# G603A.net
KiCad netlist of a schematic drawn in EAGLE
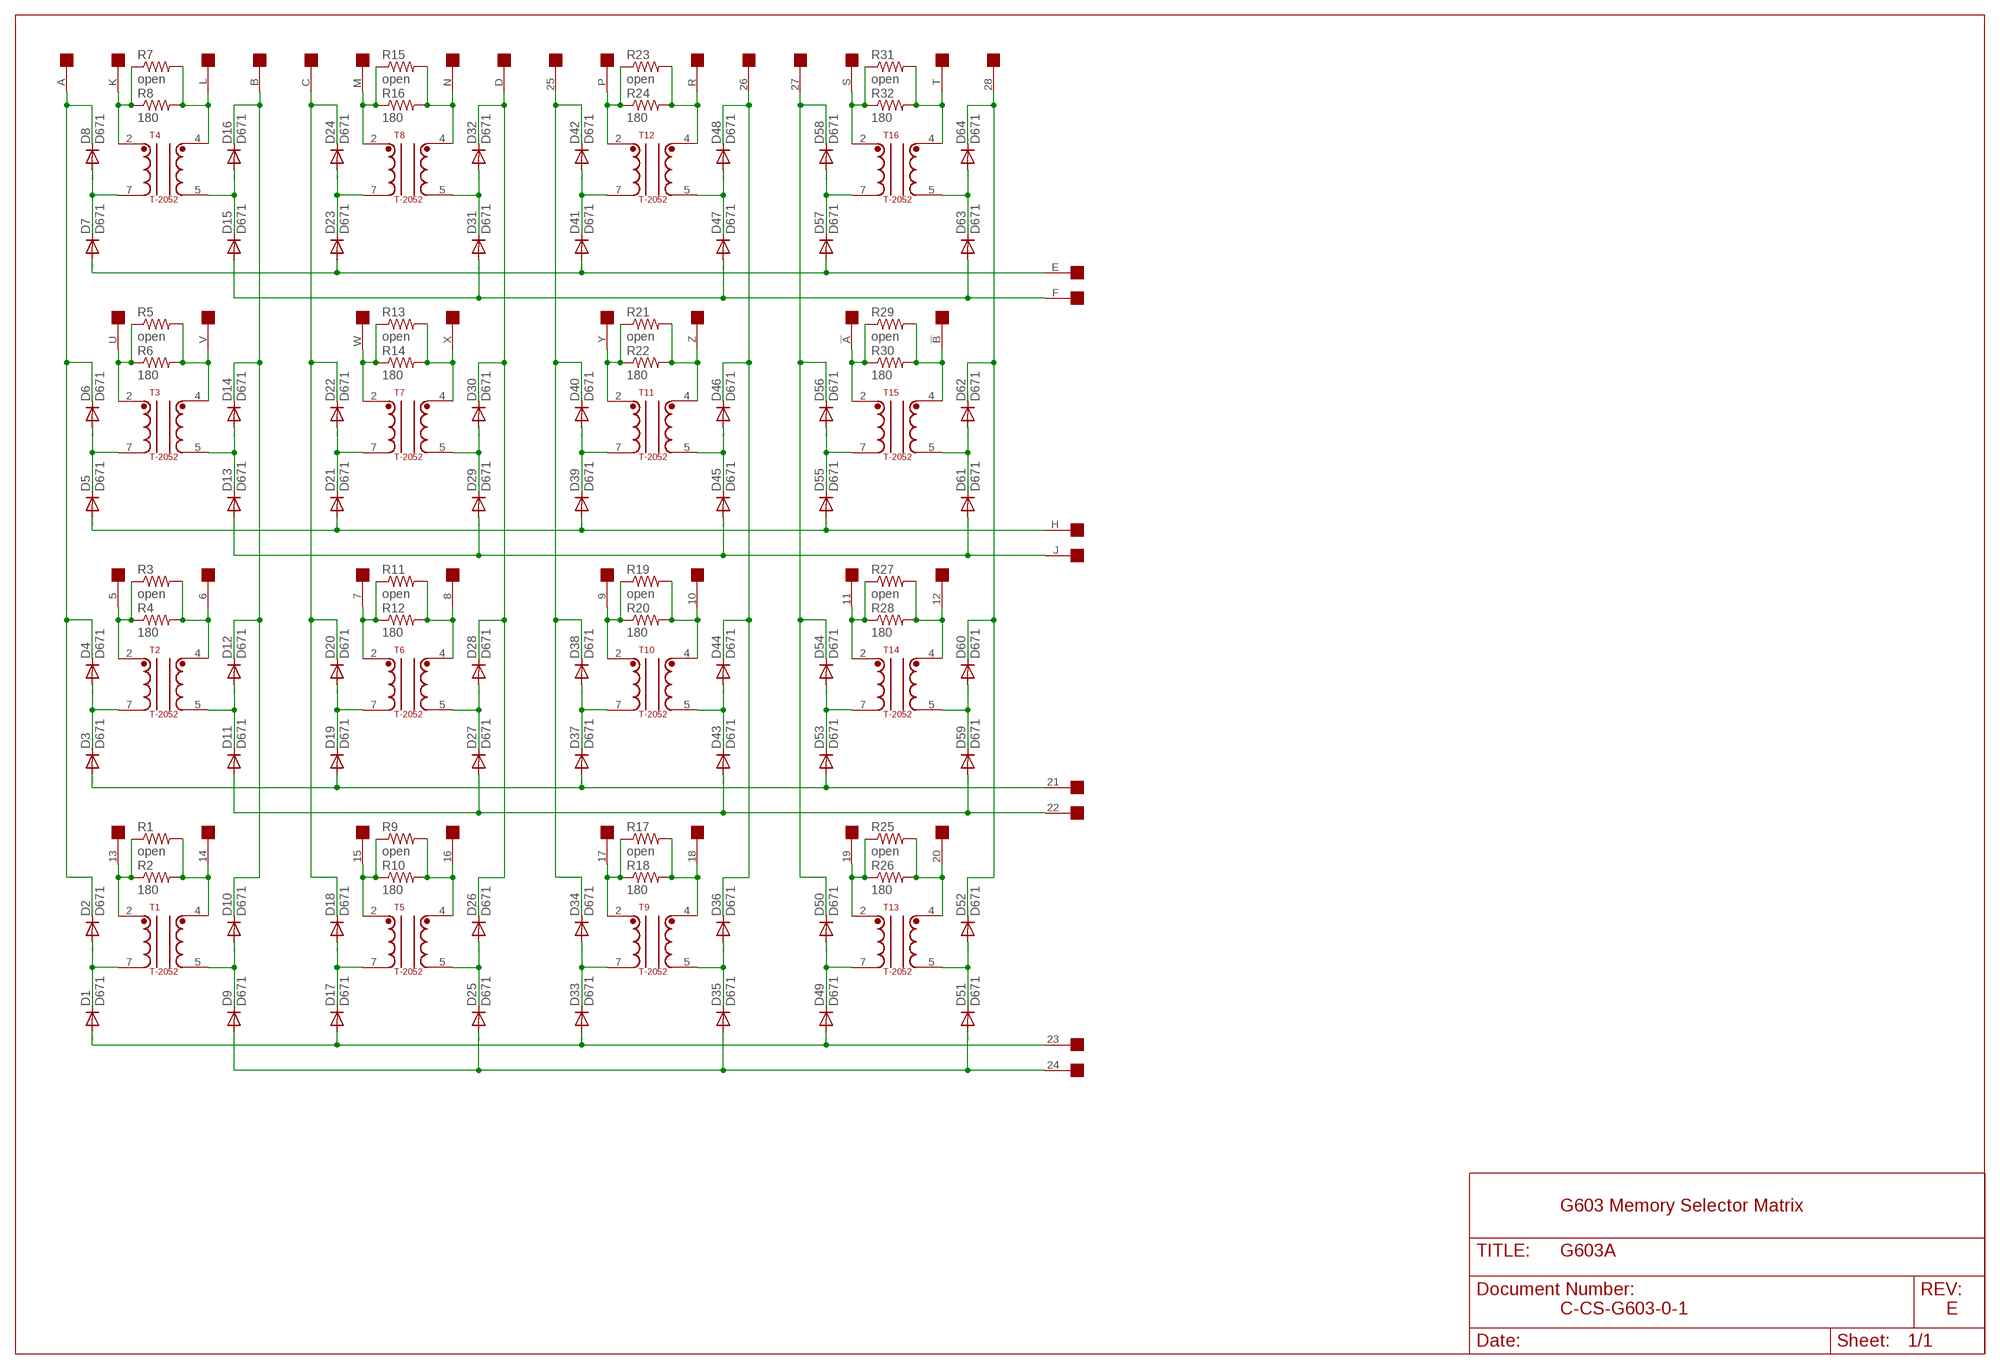
[diagram p0: schematic, sheet 1]

(export (version "E")
  (design (tool "Eeschema 10.0.6"))
  (components
    (comp (ref "D1")
      (value "D671")
      (footprint "eagle-import:DO35-10")
      (libsource (lib "eagle-import") (part "DIODE-DO35-10"))
    )
    (comp (ref "D2")
      (value "D671")
      (footprint "eagle-import:DO35-10")
      (libsource (lib "eagle-import") (part "DIODE-DO35-10"))
    )
    (comp (ref "D3")
      (value "D671")
      (footprint "eagle-import:DO35-10")
      (libsource (lib "eagle-import") (part "DIODE-DO35-10"))
    )
    (comp (ref "D4")
      (value "D671")
      (footprint "eagle-import:DO35-10")
      (libsource (lib "eagle-import") (part "DIODE-DO35-10"))
    )
    (comp (ref "D5")
      (value "D671")
      (footprint "eagle-import:DO35-10")
      (libsource (lib "eagle-import") (part "DIODE-DO35-10"))
    )
    (comp (ref "D6")
      (value "D671")
      (footprint "eagle-import:DO35-10")
      (libsource (lib "eagle-import") (part "DIODE-DO35-10"))
    )
    (comp (ref "D7")
      (value "D671")
      (footprint "eagle-import:DO35-10")
      (libsource (lib "eagle-import") (part "DIODE-DO35-10"))
    )
    (comp (ref "D8")
      (value "D671")
      (footprint "eagle-import:DO35-10")
      (libsource (lib "eagle-import") (part "DIODE-DO35-10"))
    )
    (comp (ref "D9")
      (value "D671")
      (footprint "eagle-import:DO35-10")
      (libsource (lib "eagle-import") (part "DIODE-DO35-10"))
    )
    (comp (ref "D10")
      (value "D671")
      (footprint "eagle-import:DO35-10")
      (libsource (lib "eagle-import") (part "DIODE-DO35-10"))
    )
    (comp (ref "D11")
      (value "D671")
      (footprint "eagle-import:DO35-10")
      (libsource (lib "eagle-import") (part "DIODE-DO35-10"))
    )
    (comp (ref "D12")
      (value "D671")
      (footprint "eagle-import:DO35-10")
      (libsource (lib "eagle-import") (part "DIODE-DO35-10"))
    )
    (comp (ref "D13")
      (value "D671")
      (footprint "eagle-import:DO35-10")
      (libsource (lib "eagle-import") (part "DIODE-DO35-10"))
    )
    (comp (ref "D14")
      (value "D671")
      (footprint "eagle-import:DO35-10")
      (libsource (lib "eagle-import") (part "DIODE-DO35-10"))
    )
    (comp (ref "D15")
      (value "D671")
      (footprint "eagle-import:DO35-10")
      (libsource (lib "eagle-import") (part "DIODE-DO35-10"))
    )
    (comp (ref "D16")
      (value "D671")
      (footprint "eagle-import:DO35-10")
      (libsource (lib "eagle-import") (part "DIODE-DO35-10"))
    )
    (comp (ref "D17")
      (value "D671")
      (footprint "eagle-import:DO35-10")
      (libsource (lib "eagle-import") (part "DIODE-DO35-10"))
    )
    (comp (ref "D18")
      (value "D671")
      (footprint "eagle-import:DO35-10")
      (libsource (lib "eagle-import") (part "DIODE-DO35-10"))
    )
    (comp (ref "D19")
      (value "D671")
      (footprint "eagle-import:DO35-10")
      (libsource (lib "eagle-import") (part "DIODE-DO35-10"))
    )
    (comp (ref "D20")
      (value "D671")
      (footprint "eagle-import:DO35-10")
      (libsource (lib "eagle-import") (part "DIODE-DO35-10"))
    )
    (comp (ref "D21")
      (value "D671")
      (footprint "eagle-import:DO35-10")
      (libsource (lib "eagle-import") (part "DIODE-DO35-10"))
    )
    (comp (ref "D22")
      (value "D671")
      (footprint "eagle-import:DO35-10")
      (libsource (lib "eagle-import") (part "DIODE-DO35-10"))
    )
    (comp (ref "D23")
      (value "D671")
      (footprint "eagle-import:DO35-10")
      (libsource (lib "eagle-import") (part "DIODE-DO35-10"))
    )
    (comp (ref "D24")
      (value "D671")
      (footprint "eagle-import:DO35-10")
      (libsource (lib "eagle-import") (part "DIODE-DO35-10"))
    )
    (comp (ref "D25")
      (value "D671")
      (footprint "eagle-import:DO35-10")
      (libsource (lib "eagle-import") (part "DIODE-DO35-10"))
    )
    (comp (ref "D26")
      (value "D671")
      (footprint "eagle-import:DO35-10")
      (libsource (lib "eagle-import") (part "DIODE-DO35-10"))
    )
    (comp (ref "D27")
      (value "D671")
      (footprint "eagle-import:DO35-10")
      (libsource (lib "eagle-import") (part "DIODE-DO35-10"))
    )
    (comp (ref "D28")
      (value "D671")
      (footprint "eagle-import:DO35-10")
      (libsource (lib "eagle-import") (part "DIODE-DO35-10"))
    )
    (comp (ref "D29")
      (value "D671")
      (footprint "eagle-import:DO35-10")
      (libsource (lib "eagle-import") (part "DIODE-DO35-10"))
    )
    (comp (ref "D30")
      (value "D671")
      (footprint "eagle-import:DO35-10")
      (libsource (lib "eagle-import") (part "DIODE-DO35-10"))
    )
    (comp (ref "D31")
      (value "D671")
      (footprint "eagle-import:DO35-10")
      (libsource (lib "eagle-import") (part "DIODE-DO35-10"))
    )
    (comp (ref "D32")
      (value "D671")
      (footprint "eagle-import:DO35-10")
      (libsource (lib "eagle-import") (part "DIODE-DO35-10"))
    )
    (comp (ref "D33")
      (value "D671")
      (footprint "eagle-import:DO35-10")
      (libsource (lib "eagle-import") (part "DIODE-DO35-10"))
    )
    (comp (ref "D34")
      (value "D671")
      (footprint "eagle-import:DO35-10")
      (libsource (lib "eagle-import") (part "DIODE-DO35-10"))
    )
    (comp (ref "D35")
      (value "D671")
      (footprint "eagle-import:DO35-10")
      (libsource (lib "eagle-import") (part "DIODE-DO35-10"))
    )
    (comp (ref "D36")
      (value "D671")
      (footprint "eagle-import:DO35-10")
      (libsource (lib "eagle-import") (part "DIODE-DO35-10"))
    )
    (comp (ref "D37")
      (value "D671")
      (footprint "eagle-import:DO35-10")
      (libsource (lib "eagle-import") (part "DIODE-DO35-10"))
    )
    (comp (ref "D38")
      (value "D671")
      (footprint "eagle-import:DO35-10")
      (libsource (lib "eagle-import") (part "DIODE-DO35-10"))
    )
    (comp (ref "D39")
      (value "D671")
      (footprint "eagle-import:DO35-10")
      (libsource (lib "eagle-import") (part "DIODE-DO35-10"))
    )
    (comp (ref "D40")
      (value "D671")
      (footprint "eagle-import:DO35-10")
      (libsource (lib "eagle-import") (part "DIODE-DO35-10"))
    )
    (comp (ref "D41")
      (value "D671")
      (footprint "eagle-import:DO35-10")
      (libsource (lib "eagle-import") (part "DIODE-DO35-10"))
    )
    (comp (ref "D42")
      (value "D671")
      (footprint "eagle-import:DO35-10")
      (libsource (lib "eagle-import") (part "DIODE-DO35-10"))
    )
    (comp (ref "D43")
      (value "D671")
      (footprint "eagle-import:DO35-10")
      (libsource (lib "eagle-import") (part "DIODE-DO35-10"))
    )
    (comp (ref "D44")
      (value "D671")
      (footprint "eagle-import:DO35-10")
      (libsource (lib "eagle-import") (part "DIODE-DO35-10"))
    )
    (comp (ref "D45")
      (value "D671")
      (footprint "eagle-import:DO35-10")
      (libsource (lib "eagle-import") (part "DIODE-DO35-10"))
    )
    (comp (ref "D46")
      (value "D671")
      (footprint "eagle-import:DO35-10")
      (libsource (lib "eagle-import") (part "DIODE-DO35-10"))
    )
    (comp (ref "D47")
      (value "D671")
      (footprint "eagle-import:DO35-10")
      (libsource (lib "eagle-import") (part "DIODE-DO35-10"))
    )
    (comp (ref "D48")
      (value "D671")
      (footprint "eagle-import:DO35-10")
      (libsource (lib "eagle-import") (part "DIODE-DO35-10"))
    )
    (comp (ref "D49")
      (value "D671")
      (footprint "eagle-import:DO35-10")
      (libsource (lib "eagle-import") (part "DIODE-DO35-10"))
    )
    (comp (ref "D50")
      (value "D671")
      (footprint "eagle-import:DO35-10")
      (libsource (lib "eagle-import") (part "DIODE-DO35-10"))
    )
    (comp (ref "D51")
      (value "D671")
      (footprint "eagle-import:DO35-10")
      (libsource (lib "eagle-import") (part "DIODE-DO35-10"))
    )
    (comp (ref "D52")
      (value "D671")
      (footprint "eagle-import:DO35-10")
      (libsource (lib "eagle-import") (part "DIODE-DO35-10"))
    )
    (comp (ref "D53")
      (value "D671")
      (footprint "eagle-import:DO35-10")
      (libsource (lib "eagle-import") (part "DIODE-DO35-10"))
    )
    (comp (ref "D54")
      (value "D671")
      (footprint "eagle-import:DO35-10")
      (libsource (lib "eagle-import") (part "DIODE-DO35-10"))
    )
    (comp (ref "D55")
      (value "D671")
      (footprint "eagle-import:DO35-10")
      (libsource (lib "eagle-import") (part "DIODE-DO35-10"))
    )
    (comp (ref "D56")
      (value "D671")
      (footprint "eagle-import:DO35-10")
      (libsource (lib "eagle-import") (part "DIODE-DO35-10"))
    )
    (comp (ref "D57")
      (value "D671")
      (footprint "eagle-import:DO35-10")
      (libsource (lib "eagle-import") (part "DIODE-DO35-10"))
    )
    (comp (ref "D58")
      (value "D671")
      (footprint "eagle-import:DO35-10")
      (libsource (lib "eagle-import") (part "DIODE-DO35-10"))
    )
    (comp (ref "D59")
      (value "D671")
      (footprint "eagle-import:DO35-10")
      (libsource (lib "eagle-import") (part "DIODE-DO35-10"))
    )
    (comp (ref "D60")
      (value "D671")
      (footprint "eagle-import:DO35-10")
      (libsource (lib "eagle-import") (part "DIODE-DO35-10"))
    )
    (comp (ref "D61")
      (value "D671")
      (footprint "eagle-import:DO35-10")
      (libsource (lib "eagle-import") (part "DIODE-DO35-10"))
    )
    (comp (ref "D62")
      (value "D671")
      (footprint "eagle-import:DO35-10")
      (libsource (lib "eagle-import") (part "DIODE-DO35-10"))
    )
    (comp (ref "D63")
      (value "D671")
      (footprint "eagle-import:DO35-10")
      (libsource (lib "eagle-import") (part "DIODE-DO35-10"))
    )
    (comp (ref "D64")
      (value "D671")
      (footprint "eagle-import:DO35-10")
      (libsource (lib "eagle-import") (part "DIODE-DO35-10"))
    )
    (comp (ref "EDGE1")
      (value "MEM8")
      (footprint "eagle-import:MEM8")
      (libsource (lib "eagle-import") (part "MEM8"))
    )
    (comp (ref "R1")
      (value "open")
      (footprint "eagle-import:0207_10")
      (libsource (lib "eagle-import") (part "R-US_0207/10"))
    )
    (comp (ref "R2")
      (value "180")
      (footprint "eagle-import:0207_10")
      (libsource (lib "eagle-import") (part "R-US_0207/10"))
    )
    (comp (ref "R3")
      (value "open")
      (footprint "eagle-import:0207_10")
      (libsource (lib "eagle-import") (part "R-US_0207/10"))
    )
    (comp (ref "R4")
      (value "180")
      (footprint "eagle-import:0207_10")
      (libsource (lib "eagle-import") (part "R-US_0207/10"))
    )
    (comp (ref "R5")
      (value "open")
      (footprint "eagle-import:0207_10")
      (libsource (lib "eagle-import") (part "R-US_0207/10"))
    )
    (comp (ref "R6")
      (value "180")
      (footprint "eagle-import:0207_10")
      (libsource (lib "eagle-import") (part "R-US_0207/10"))
    )
    (comp (ref "R7")
      (value "open")
      (footprint "eagle-import:0207_10")
      (libsource (lib "eagle-import") (part "R-US_0207/10"))
    )
    (comp (ref "R8")
      (value "180")
      (footprint "eagle-import:0207_10")
      (libsource (lib "eagle-import") (part "R-US_0207/10"))
    )
    (comp (ref "R9")
      (value "open")
      (footprint "eagle-import:0207_10")
      (libsource (lib "eagle-import") (part "R-US_0207/10"))
    )
    (comp (ref "R10")
      (value "180")
      (footprint "eagle-import:0207_10")
      (libsource (lib "eagle-import") (part "R-US_0207/10"))
    )
    (comp (ref "R11")
      (value "open")
      (footprint "eagle-import:0207_10")
      (libsource (lib "eagle-import") (part "R-US_0207/10"))
    )
    (comp (ref "R12")
      (value "180")
      (footprint "eagle-import:0207_10")
      (libsource (lib "eagle-import") (part "R-US_0207/10"))
    )
    (comp (ref "R13")
      (value "open")
      (footprint "eagle-import:0207_10")
      (libsource (lib "eagle-import") (part "R-US_0207/10"))
    )
    (comp (ref "R14")
      (value "180")
      (footprint "eagle-import:0207_10")
      (libsource (lib "eagle-import") (part "R-US_0207/10"))
    )
    (comp (ref "R15")
      (value "open")
      (footprint "eagle-import:0207_10")
      (libsource (lib "eagle-import") (part "R-US_0207/10"))
    )
    (comp (ref "R16")
      (value "180")
      (footprint "eagle-import:0207_10")
      (libsource (lib "eagle-import") (part "R-US_0207/10"))
    )
    (comp (ref "R17")
      (value "open")
      (footprint "eagle-import:0207_10")
      (libsource (lib "eagle-import") (part "R-US_0207/10"))
    )
    (comp (ref "R18")
      (value "180")
      (footprint "eagle-import:0207_10")
      (libsource (lib "eagle-import") (part "R-US_0207/10"))
    )
    (comp (ref "R19")
      (value "open")
      (footprint "eagle-import:0207_10")
      (libsource (lib "eagle-import") (part "R-US_0207/10"))
    )
    (comp (ref "R20")
      (value "180")
      (footprint "eagle-import:0207_10")
      (libsource (lib "eagle-import") (part "R-US_0207/10"))
    )
    (comp (ref "R21")
      (value "open")
      (footprint "eagle-import:0207_10")
      (libsource (lib "eagle-import") (part "R-US_0207/10"))
    )
    (comp (ref "R22")
      (value "180")
      (footprint "eagle-import:0207_10")
      (libsource (lib "eagle-import") (part "R-US_0207/10"))
    )
    (comp (ref "R23")
      (value "open")
      (footprint "eagle-import:0207_10")
      (libsource (lib "eagle-import") (part "R-US_0207/10"))
    )
    (comp (ref "R24")
      (value "180")
      (footprint "eagle-import:0207_10")
      (libsource (lib "eagle-import") (part "R-US_0207/10"))
    )
    (comp (ref "R25")
      (value "open")
      (footprint "eagle-import:0207_10")
      (libsource (lib "eagle-import") (part "R-US_0207/10"))
    )
    (comp (ref "R26")
      (value "180")
      (footprint "eagle-import:0207_10")
      (libsource (lib "eagle-import") (part "R-US_0207/10"))
    )
    (comp (ref "R27")
      (value "open")
      (footprint "eagle-import:0207_10")
      (libsource (lib "eagle-import") (part "R-US_0207/10"))
    )
    (comp (ref "R28")
      (value "180")
      (footprint "eagle-import:0207_10")
      (libsource (lib "eagle-import") (part "R-US_0207/10"))
    )
    (comp (ref "R29")
      (value "open")
      (footprint "eagle-import:0207_10")
      (libsource (lib "eagle-import") (part "R-US_0207/10"))
    )
    (comp (ref "R30")
      (value "180")
      (footprint "eagle-import:0207_10")
      (libsource (lib "eagle-import") (part "R-US_0207/10"))
    )
    (comp (ref "R31")
      (value "open")
      (footprint "eagle-import:0207_10")
      (libsource (lib "eagle-import") (part "R-US_0207/10"))
    )
    (comp (ref "R32")
      (value "180")
      (footprint "eagle-import:0207_10")
      (libsource (lib "eagle-import") (part "R-US_0207/10"))
    )
    (comp (ref "T1")
      (value "T-2052")
      (footprint "eagle-import:TRANSFORMER")
      (libsource (lib "eagle-import") (part "T-2052"))
    )
    (comp (ref "T2")
      (value "T-2052")
      (footprint "eagle-import:TRANSFORMER")
      (libsource (lib "eagle-import") (part "T-2052"))
    )
    (comp (ref "T3")
      (value "T-2052")
      (footprint "eagle-import:TRANSFORMER")
      (libsource (lib "eagle-import") (part "T-2052"))
    )
    (comp (ref "T4")
      (value "T-2052")
      (footprint "eagle-import:TRANSFORMER")
      (libsource (lib "eagle-import") (part "T-2052"))
    )
    (comp (ref "T5")
      (value "T-2052")
      (footprint "eagle-import:TRANSFORMER")
      (libsource (lib "eagle-import") (part "T-2052"))
    )
    (comp (ref "T6")
      (value "T-2052")
      (footprint "eagle-import:TRANSFORMER")
      (libsource (lib "eagle-import") (part "T-2052"))
    )
    (comp (ref "T7")
      (value "T-2052")
      (footprint "eagle-import:TRANSFORMER")
      (libsource (lib "eagle-import") (part "T-2052"))
    )
    (comp (ref "T8")
      (value "T-2052")
      (footprint "eagle-import:TRANSFORMER")
      (libsource (lib "eagle-import") (part "T-2052"))
    )
    (comp (ref "T9")
      (value "T-2052")
      (footprint "eagle-import:TRANSFORMER")
      (libsource (lib "eagle-import") (part "T-2052"))
    )
    (comp (ref "T10")
      (value "T-2052")
      (footprint "eagle-import:TRANSFORMER")
      (libsource (lib "eagle-import") (part "T-2052"))
    )
    (comp (ref "T11")
      (value "T-2052")
      (footprint "eagle-import:TRANSFORMER")
      (libsource (lib "eagle-import") (part "T-2052"))
    )
    (comp (ref "T12")
      (value "T-2052")
      (footprint "eagle-import:TRANSFORMER")
      (libsource (lib "eagle-import") (part "T-2052"))
    )
    (comp (ref "T13")
      (value "T-2052")
      (footprint "eagle-import:TRANSFORMER")
      (libsource (lib "eagle-import") (part "T-2052"))
    )
    (comp (ref "T14")
      (value "T-2052")
      (footprint "eagle-import:TRANSFORMER")
      (libsource (lib "eagle-import") (part "T-2052"))
    )
    (comp (ref "T15")
      (value "T-2052")
      (footprint "eagle-import:TRANSFORMER")
      (libsource (lib "eagle-import") (part "T-2052"))
    )
    (comp (ref "T16")
      (value "T-2052")
      (footprint "eagle-import:TRANSFORMER")
      (libsource (lib "eagle-import") (part "T-2052"))
    )
  )
  (nets
    (net (code "1") (name "Net-(EDGE1A-1)") (class "Default")
      (node (ref "EDGE1") (pin "!A") (pinfunction "1_!A") (pintype "bidirectional"))
      (node (ref "R29") (pin "1") (pinfunction "1_1") (pintype "passive"))
      (node (ref "R30") (pin "1") (pinfunction "1_1") (pintype "passive"))
      (node (ref "T15") (pin "2") (pinfunction "P$2_2") (pintype "passive"))
    )
    (net (code "2") (name "Net-(EDGE1AA-1)") (class "Default")
      (node (ref "D52") (pin "C") (pinfunction "C_C") (pintype "passive"))
      (node (ref "D60") (pin "C") (pinfunction "C_C") (pintype "passive"))
      (node (ref "D62") (pin "C") (pinfunction "C_C") (pintype "passive"))
      (node (ref "D64") (pin "C") (pinfunction "C_C") (pintype "passive"))
      (node (ref "EDGE1") (pin "28") (pinfunction "1_28") (pintype "bidirectional"))
    )
    (net (code "3") (name "Net-(EDGE1AD-1)") (class "Default")
      (node (ref "EDGE1") (pin "5") (pinfunction "1_5") (pintype "bidirectional"))
      (node (ref "R3") (pin "1") (pinfunction "1_1") (pintype "passive"))
      (node (ref "R4") (pin "1") (pinfunction "1_1") (pintype "passive"))
      (node (ref "T2") (pin "2") (pinfunction "P$2_2") (pintype "passive"))
    )
    (net (code "4") (name "Net-(EDGE1AE-1)") (class "Default")
      (node (ref "EDGE1") (pin "6") (pinfunction "1_6") (pintype "bidirectional"))
      (node (ref "R3") (pin "2") (pinfunction "2_2") (pintype "passive"))
      (node (ref "R4") (pin "2") (pinfunction "2_2") (pintype "passive"))
      (node (ref "T2") (pin "4") (pinfunction "P$4_4") (pintype "passive"))
    )
    (net (code "5") (name "Net-(EDGE1AF-1)") (class "Default")
      (node (ref "EDGE1") (pin "7") (pinfunction "1_7") (pintype "bidirectional"))
      (node (ref "R11") (pin "1") (pinfunction "1_1") (pintype "passive"))
      (node (ref "R12") (pin "1") (pinfunction "1_1") (pintype "passive"))
      (node (ref "T6") (pin "2") (pinfunction "P$2_2") (pintype "passive"))
    )
    (net (code "6") (name "Net-(EDGE1AG-1)") (class "Default")
      (node (ref "EDGE1") (pin "8") (pinfunction "1_8") (pintype "bidirectional"))
      (node (ref "R11") (pin "2") (pinfunction "2_2") (pintype "passive"))
      (node (ref "R12") (pin "2") (pinfunction "2_2") (pintype "passive"))
      (node (ref "T6") (pin "4") (pinfunction "P$4_4") (pintype "passive"))
    )
    (net (code "7") (name "Net-(EDGE1AH-1)") (class "Default")
      (node (ref "EDGE1") (pin "9") (pinfunction "1_9") (pintype "bidirectional"))
      (node (ref "R19") (pin "1") (pinfunction "1_1") (pintype "passive"))
      (node (ref "R20") (pin "1") (pinfunction "1_1") (pintype "passive"))
      (node (ref "T10") (pin "2") (pinfunction "P$2_2") (pintype "passive"))
    )
    (net (code "8") (name "Net-(EDGE1AI-1)") (class "Default")
      (node (ref "D2") (pin "C") (pinfunction "C_C") (pintype "passive"))
      (node (ref "D4") (pin "C") (pinfunction "C_C") (pintype "passive"))
      (node (ref "D6") (pin "C") (pinfunction "C_C") (pintype "passive"))
      (node (ref "D8") (pin "C") (pinfunction "C_C") (pintype "passive"))
      (node (ref "EDGE1") (pin "A") (pinfunction "1_A") (pintype "bidirectional"))
    )
    (net (code "9") (name "Net-(EDGE1AJ-1)") (class "Default")
      (node (ref "D10") (pin "C") (pinfunction "C_C") (pintype "passive"))
      (node (ref "D12") (pin "C") (pinfunction "C_C") (pintype "passive"))
      (node (ref "D14") (pin "C") (pinfunction "C_C") (pintype "passive"))
      (node (ref "D16") (pin "C") (pinfunction "C_C") (pintype "passive"))
      (node (ref "EDGE1") (pin "B") (pinfunction "1_B") (pintype "bidirectional"))
    )
    (net (code "10") (name "Net-(EDGE1AK-1)") (class "Default")
      (node (ref "D18") (pin "C") (pinfunction "C_C") (pintype "passive"))
      (node (ref "D20") (pin "C") (pinfunction "C_C") (pintype "passive"))
      (node (ref "D22") (pin "C") (pinfunction "C_C") (pintype "passive"))
      (node (ref "D24") (pin "C") (pinfunction "C_C") (pintype "passive"))
      (node (ref "EDGE1") (pin "C") (pinfunction "1_C") (pintype "bidirectional"))
    )
    (net (code "11") (name "Net-(EDGE1AL-1)") (class "Default")
      (node (ref "D26") (pin "C") (pinfunction "C_C") (pintype "passive"))
      (node (ref "D28") (pin "C") (pinfunction "C_C") (pintype "passive"))
      (node (ref "D30") (pin "C") (pinfunction "C_C") (pintype "passive"))
      (node (ref "D32") (pin "C") (pinfunction "C_C") (pintype "passive"))
      (node (ref "EDGE1") (pin "D") (pinfunction "1_D") (pintype "bidirectional"))
    )
    (net (code "12") (name "Net-(EDGE1AM-1)") (class "Default")
      (node (ref "D23") (pin "A") (pinfunction "A_A") (pintype "passive"))
      (node (ref "D41") (pin "A") (pinfunction "A_A") (pintype "passive"))
      (node (ref "D57") (pin "A") (pinfunction "A_A") (pintype "passive"))
      (node (ref "D7") (pin "A") (pinfunction "A_A") (pintype "passive"))
      (node (ref "EDGE1") (pin "E") (pinfunction "1_E") (pintype "bidirectional"))
    )
    (net (code "13") (name "Net-(EDGE1AN-1)") (class "Default")
      (node (ref "D15") (pin "A") (pinfunction "A_A") (pintype "passive"))
      (node (ref "D31") (pin "A") (pinfunction "A_A") (pintype "passive"))
      (node (ref "D47") (pin "A") (pinfunction "A_A") (pintype "passive"))
      (node (ref "D63") (pin "A") (pinfunction "A_A") (pintype "passive"))
      (node (ref "EDGE1") (pin "F") (pinfunction "1_F") (pintype "bidirectional"))
    )
    (net (code "14") (name "Net-(EDGE1AO-1)") (class "Default")
      (node (ref "D21") (pin "A") (pinfunction "A_A") (pintype "passive"))
      (node (ref "D39") (pin "A") (pinfunction "A_A") (pintype "passive"))
      (node (ref "D5") (pin "A") (pinfunction "A_A") (pintype "passive"))
      (node (ref "D55") (pin "A") (pinfunction "A_A") (pintype "passive"))
      (node (ref "EDGE1") (pin "H") (pinfunction "1_H") (pintype "bidirectional"))
    )
    (net (code "15") (name "Net-(EDGE1AP-1)") (class "Default")
      (node (ref "D13") (pin "A") (pinfunction "A_A") (pintype "passive"))
      (node (ref "D29") (pin "A") (pinfunction "A_A") (pintype "passive"))
      (node (ref "D45") (pin "A") (pinfunction "A_A") (pintype "passive"))
      (node (ref "D61") (pin "A") (pinfunction "A_A") (pintype "passive"))
      (node (ref "EDGE1") (pin "J") (pinfunction "1_J") (pintype "bidirectional"))
    )
    (net (code "16") (name "Net-(EDGE1AQ-1)") (class "Default")
      (node (ref "EDGE1") (pin "K") (pinfunction "1_K") (pintype "bidirectional"))
      (node (ref "R7") (pin "1") (pinfunction "1_1") (pintype "passive"))
      (node (ref "R8") (pin "1") (pinfunction "1_1") (pintype "passive"))
      (node (ref "T4") (pin "2") (pinfunction "P$2_2") (pintype "passive"))
    )
    (net (code "17") (name "Net-(EDGE1AR-1)") (class "Default")
      (node (ref "EDGE1") (pin "L") (pinfunction "1_L") (pintype "bidirectional"))
      (node (ref "R7") (pin "2") (pinfunction "2_2") (pintype "passive"))
      (node (ref "R8") (pin "2") (pinfunction "2_2") (pintype "passive"))
      (node (ref "T4") (pin "4") (pinfunction "P$4_4") (pintype "passive"))
    )
    (net (code "18") (name "Net-(EDGE1AS-1)") (class "Default")
      (node (ref "EDGE1") (pin "M") (pinfunction "1_M") (pintype "bidirectional"))
      (node (ref "R15") (pin "1") (pinfunction "1_1") (pintype "passive"))
      (node (ref "R16") (pin "1") (pinfunction "1_1") (pintype "passive"))
      (node (ref "T8") (pin "2") (pinfunction "P$2_2") (pintype "passive"))
    )
    (net (code "19") (name "Net-(EDGE1AT-1)") (class "Default")
      (node (ref "EDGE1") (pin "N") (pinfunction "1_N") (pintype "bidirectional"))
      (node (ref "R15") (pin "2") (pinfunction "2_2") (pintype "passive"))
      (node (ref "R16") (pin "2") (pinfunction "2_2") (pintype "passive"))
      (node (ref "T8") (pin "4") (pinfunction "P$4_4") (pintype "passive"))
    )
    (net (code "20") (name "Net-(EDGE1AU-1)") (class "Default")
      (node (ref "EDGE1") (pin "P") (pinfunction "1_P") (pintype "bidirectional"))
      (node (ref "R23") (pin "1") (pinfunction "1_1") (pintype "passive"))
      (node (ref "R24") (pin "1") (pinfunction "1_1") (pintype "passive"))
      (node (ref "T12") (pin "2") (pinfunction "P$2_2") (pintype "passive"))
    )
    (net (code "21") (name "Net-(EDGE1AV-1)") (class "Default")
      (node (ref "EDGE1") (pin "R") (pinfunction "1_R") (pintype "bidirectional"))
      (node (ref "R23") (pin "2") (pinfunction "2_2") (pintype "passive"))
      (node (ref "R24") (pin "2") (pinfunction "2_2") (pintype "passive"))
      (node (ref "T12") (pin "4") (pinfunction "P$4_4") (pintype "passive"))
    )
    (net (code "22") (name "Net-(EDGE1AW-1)") (class "Default")
      (node (ref "EDGE1") (pin "S") (pinfunction "1_S") (pintype "bidirectional"))
      (node (ref "R31") (pin "1") (pinfunction "1_1") (pintype "passive"))
      (node (ref "R32") (pin "1") (pinfunction "1_1") (pintype "passive"))
      (node (ref "T16") (pin "2") (pinfunction "P$2_2") (pintype "passive"))
    )
    (net (code "23") (name "Net-(EDGE1AX-1)") (class "Default")
      (node (ref "EDGE1") (pin "T") (pinfunction "1_T") (pintype "bidirectional"))
      (node (ref "R31") (pin "2") (pinfunction "2_2") (pintype "passive"))
      (node (ref "R32") (pin "2") (pinfunction "2_2") (pintype "passive"))
      (node (ref "T16") (pin "4") (pinfunction "P$4_4") (pintype "passive"))
    )
    (net (code "24") (name "Net-(EDGE1AY-1)") (class "Default")
      (node (ref "EDGE1") (pin "U") (pinfunction "1_U") (pintype "bidirectional"))
      (node (ref "R5") (pin "1") (pinfunction "1_1") (pintype "passive"))
      (node (ref "R6") (pin "1") (pinfunction "1_1") (pintype "passive"))
      (node (ref "T3") (pin "2") (pinfunction "P$2_2") (pintype "passive"))
    )
    (net (code "25") (name "Net-(EDGE1AZ-1)") (class "Default")
      (node (ref "EDGE1") (pin "V") (pinfunction "1_V") (pintype "bidirectional"))
      (node (ref "R5") (pin "2") (pinfunction "2_2") (pintype "passive"))
      (node (ref "R6") (pin "2") (pinfunction "2_2") (pintype "passive"))
      (node (ref "T3") (pin "4") (pinfunction "P$4_4") (pintype "passive"))
    )
    (net (code "26") (name "Net-(EDGE1B-1)") (class "Default")
      (node (ref "EDGE1") (pin "!B") (pinfunction "1_!B") (pintype "bidirectional"))
      (node (ref "R29") (pin "2") (pinfunction "2_2") (pintype "passive"))
      (node (ref "R30") (pin "2") (pinfunction "2_2") (pintype "passive"))
      (node (ref "T15") (pin "4") (pinfunction "P$4_4") (pintype "passive"))
    )
    (net (code "27") (name "Net-(EDGE1BA-1)") (class "Default")
      (node (ref "EDGE1") (pin "W") (pinfunction "1_W") (pintype "bidirectional"))
      (node (ref "R13") (pin "1") (pinfunction "1_1") (pintype "passive"))
      (node (ref "R14") (pin "1") (pinfunction "1_1") (pintype "passive"))
      (node (ref "T7") (pin "2") (pinfunction "P$2_2") (pintype "passive"))
    )
    (net (code "28") (name "Net-(EDGE1BB-1)") (class "Default")
      (node (ref "EDGE1") (pin "X") (pinfunction "1_X") (pintype "bidirectional"))
      (node (ref "R13") (pin "2") (pinfunction "2_2") (pintype "passive"))
      (node (ref "R14") (pin "2") (pinfunction "2_2") (pintype "passive"))
      (node (ref "T7") (pin "4") (pinfunction "P$4_4") (pintype "passive"))
    )
    (net (code "29") (name "Net-(EDGE1BC-1)") (class "Default")
      (node (ref "EDGE1") (pin "Y") (pinfunction "1_Y") (pintype "bidirectional"))
      (node (ref "R21") (pin "1") (pinfunction "1_1") (pintype "passive"))
      (node (ref "R22") (pin "1") (pinfunction "1_1") (pintype "passive"))
      (node (ref "T11") (pin "2") (pinfunction "P$2_2") (pintype "passive"))
    )
    (net (code "30") (name "Net-(EDGE1BD-1)") (class "Default")
      (node (ref "EDGE1") (pin "Z") (pinfunction "1_Z") (pintype "bidirectional"))
      (node (ref "R21") (pin "2") (pinfunction "2_2") (pintype "passive"))
      (node (ref "R22") (pin "2") (pinfunction "2_2") (pintype "passive"))
      (node (ref "T11") (pin "4") (pinfunction "P$4_4") (pintype "passive"))
    )
    (net (code "31") (name "Net-(EDGE1H-1)") (class "Default")
      (node (ref "EDGE1") (pin "10") (pinfunction "1_10") (pintype "bidirectional"))
      (node (ref "R19") (pin "2") (pinfunction "2_2") (pintype "passive"))
      (node (ref "R20") (pin "2") (pinfunction "2_2") (pintype "passive"))
      (node (ref "T10") (pin "4") (pinfunction "P$4_4") (pintype "passive"))
    )
    (net (code "32") (name "Net-(EDGE1I-1)") (class "Default")
      (node (ref "EDGE1") (pin "11") (pinfunction "1_11") (pintype "bidirectional"))
      (node (ref "R27") (pin "1") (pinfunction "1_1") (pintype "passive"))
      (node (ref "R28") (pin "1") (pinfunction "1_1") (pintype "passive"))
      (node (ref "T14") (pin "2") (pinfunction "P$2_2") (pintype "passive"))
    )
    (net (code "33") (name "Net-(EDGE1J-1)") (class "Default")
      (node (ref "EDGE1") (pin "12") (pinfunction "1_12") (pintype "bidirectional"))
      (node (ref "R27") (pin "2") (pinfunction "2_2") (pintype "passive"))
      (node (ref "R28") (pin "2") (pinfunction "2_2") (pintype "passive"))
      (node (ref "T14") (pin "4") (pinfunction "P$4_4") (pintype "passive"))
    )
    (net (code "34") (name "Net-(EDGE1K-1)") (class "Default")
      (node (ref "EDGE1") (pin "13") (pinfunction "1_13") (pintype "bidirectional"))
      (node (ref "R1") (pin "1") (pinfunction "1_1") (pintype "passive"))
      (node (ref "R2") (pin "1") (pinfunction "1_1") (pintype "passive"))
      (node (ref "T1") (pin "2") (pinfunction "P$2_2") (pintype "passive"))
    )
    (net (code "35") (name "Net-(EDGE1L-1)") (class "Default")
      (node (ref "EDGE1") (pin "14") (pinfunction "1_14") (pintype "bidirectional"))
      (node (ref "R1") (pin "2") (pinfunction "2_2") (pintype "passive"))
      (node (ref "R2") (pin "2") (pinfunction "2_2") (pintype "passive"))
      (node (ref "T1") (pin "4") (pinfunction "P$4_4") (pintype "passive"))
    )
    (net (code "36") (name "Net-(EDGE1M-1)") (class "Default")
      (node (ref "EDGE1") (pin "15") (pinfunction "1_15") (pintype "bidirectional"))
      (node (ref "R10") (pin "1") (pinfunction "1_1") (pintype "passive"))
      (node (ref "R9") (pin "1") (pinfunction "1_1") (pintype "passive"))
      (node (ref "T5") (pin "2") (pinfunction "P$2_2") (pintype "passive"))
    )
    (net (code "37") (name "Net-(EDGE1N-1)") (class "Default")
      (node (ref "EDGE1") (pin "16") (pinfunction "1_16") (pintype "bidirectional"))
      (node (ref "R10") (pin "2") (pinfunction "2_2") (pintype "passive"))
      (node (ref "R9") (pin "2") (pinfunction "2_2") (pintype "passive"))
      (node (ref "T5") (pin "4") (pinfunction "P$4_4") (pintype "passive"))
    )
    (net (code "38") (name "Net-(EDGE1O-1)") (class "Default")
      (node (ref "EDGE1") (pin "17") (pinfunction "1_17") (pintype "bidirectional"))
      (node (ref "R17") (pin "1") (pinfunction "1_1") (pintype "passive"))
      (node (ref "R18") (pin "1") (pinfunction "1_1") (pintype "passive"))
      (node (ref "T9") (pin "2") (pinfunction "P$2_2") (pintype "passive"))
    )
    (net (code "39") (name "Net-(EDGE1P-1)") (class "Default")
      (node (ref "EDGE1") (pin "18") (pinfunction "1_18") (pintype "bidirectional"))
      (node (ref "R17") (pin "2") (pinfunction "2_2") (pintype "passive"))
      (node (ref "R18") (pin "2") (pinfunction "2_2") (pintype "passive"))
      (node (ref "T9") (pin "4") (pinfunction "P$4_4") (pintype "passive"))
    )
    (net (code "40") (name "Net-(EDGE1Q-1)") (class "Default")
      (node (ref "EDGE1") (pin "19") (pinfunction "1_19") (pintype "bidirectional"))
      (node (ref "R25") (pin "1") (pinfunction "1_1") (pintype "passive"))
      (node (ref "R26") (pin "1") (pinfunction "1_1") (pintype "passive"))
      (node (ref "T13") (pin "2") (pinfunction "P$2_2") (pintype "passive"))
    )
    (net (code "41") (name "Net-(EDGE1S-1)") (class "Default")
      (node (ref "EDGE1") (pin "20") (pinfunction "1_20") (pintype "bidirectional"))
      (node (ref "R25") (pin "2") (pinfunction "2_2") (pintype "passive"))
      (node (ref "R26") (pin "2") (pinfunction "2_2") (pintype "passive"))
      (node (ref "T13") (pin "4") (pinfunction "P$4_4") (pintype "passive"))
    )
    (net (code "42") (name "Net-(EDGE1T-1)") (class "Default")
      (node (ref "D19") (pin "A") (pinfunction "A_A") (pintype "passive"))
      (node (ref "D3") (pin "A") (pinfunction "A_A") (pintype "passive"))
      (node (ref "D37") (pin "A") (pinfunction "A_A") (pintype "passive"))
      (node (ref "D53") (pin "A") (pinfunction "A_A") (pintype "passive"))
      (node (ref "EDGE1") (pin "21") (pinfunction "1_21") (pintype "bidirectional"))
    )
    (net (code "43") (name "Net-(EDGE1U-1)") (class "Default")
      (node (ref "D11") (pin "A") (pinfunction "A_A") (pintype "passive"))
      (node (ref "D27") (pin "A") (pinfunction "A_A") (pintype "passive"))
      (node (ref "D43") (pin "A") (pinfunction "A_A") (pintype "passive"))
      (node (ref "D59") (pin "A") (pinfunction "A_A") (pintype "passive"))
      (node (ref "EDGE1") (pin "22") (pinfunction "1_22") (pintype "bidirectional"))
    )
    (net (code "44") (name "Net-(EDGE1V-1)") (class "Default")
      (node (ref "D1") (pin "A") (pinfunction "A_A") (pintype "passive"))
      (node (ref "D17") (pin "A") (pinfunction "A_A") (pintype "passive"))
      (node (ref "D33") (pin "A") (pinfunction "A_A") (pintype "passive"))
      (node (ref "D49") (pin "A") (pinfunction "A_A") (pintype "passive"))
      (node (ref "EDGE1") (pin "23") (pinfunction "1_23") (pintype "bidirectional"))
    )
    (net (code "45") (name "Net-(EDGE1W-1)") (class "Default")
      (node (ref "D25") (pin "A") (pinfunction "A_A") (pintype "passive"))
      (node (ref "D35") (pin "A") (pinfunction "A_A") (pintype "passive"))
      (node (ref "D51") (pin "A") (pinfunction "A_A") (pintype "passive"))
      (node (ref "D9") (pin "A") (pinfunction "A_A") (pintype "passive"))
      (node (ref "EDGE1") (pin "24") (pinfunction "1_24") (pintype "bidirectional"))
    )
    (net (code "46") (name "Net-(EDGE1X-1)") (class "Default")
      (node (ref "D34") (pin "C") (pinfunction "C_C") (pintype "passive"))
      (node (ref "D38") (pin "C") (pinfunction "C_C") (pintype "passive"))
      (node (ref "D40") (pin "C") (pinfunction "C_C") (pintype "passive"))
      (node (ref "D42") (pin "C") (pinfunction "C_C") (pintype "passive"))
      (node (ref "EDGE1") (pin "25") (pinfunction "1_25") (pintype "bidirectional"))
    )
    (net (code "47") (name "Net-(EDGE1Y-1)") (class "Default")
      (node (ref "D36") (pin "C") (pinfunction "C_C") (pintype "passive"))
      (node (ref "D44") (pin "C") (pinfunction "C_C") (pintype "passive"))
      (node (ref "D46") (pin "C") (pinfunction "C_C") (pintype "passive"))
      (node (ref "D48") (pin "C") (pinfunction "C_C") (pintype "passive"))
      (node (ref "EDGE1") (pin "26") (pinfunction "1_26") (pintype "bidirectional"))
    )
    (net (code "48") (name "Net-(EDGE1Z-1)") (class "Default")
      (node (ref "D50") (pin "C") (pinfunction "C_C") (pintype "passive"))
      (node (ref "D54") (pin "C") (pinfunction "C_C") (pintype "passive"))
      (node (ref "D56") (pin "C") (pinfunction "C_C") (pintype "passive"))
      (node (ref "D58") (pin "C") (pinfunction "C_C") (pintype "passive"))
      (node (ref "EDGE1") (pin "27") (pinfunction "1_27") (pintype "bidirectional"))
    )
    (net (code "49") (name "Net-(T1-P$5)") (class "Default")
      (node (ref "D10") (pin "A") (pinfunction "A_A") (pintype "passive"))
      (node (ref "D9") (pin "C") (pinfunction "C_C") (pintype "passive"))
      (node (ref "T1") (pin "5") (pinfunction "P$5_5") (pintype "passive"))
    )
    (net (code "50") (name "Net-(T1-P$7)") (class "Default")
      (node (ref "D1") (pin "C") (pinfunction "C_C") (pintype "passive"))
      (node (ref "D2") (pin "A") (pinfunction "A_A") (pintype "passive"))
      (node (ref "T1") (pin "7") (pinfunction "P$7_7") (pintype "passive"))
    )
    (net (code "51") (name "Net-(T2-P$5)") (class "Default")
      (node (ref "D11") (pin "C") (pinfunction "C_C") (pintype "passive"))
      (node (ref "D12") (pin "A") (pinfunction "A_A") (pintype "passive"))
      (node (ref "T2") (pin "5") (pinfunction "P$5_5") (pintype "passive"))
    )
    (net (code "52") (name "Net-(T2-P$7)") (class "Default")
      (node (ref "D3") (pin "C") (pinfunction "C_C") (pintype "passive"))
      (node (ref "D4") (pin "A") (pinfunction "A_A") (pintype "passive"))
      (node (ref "T2") (pin "7") (pinfunction "P$7_7") (pintype "passive"))
    )
    (net (code "53") (name "Net-(T3-P$5)") (class "Default")
      (node (ref "D13") (pin "C") (pinfunction "C_C") (pintype "passive"))
      (node (ref "D14") (pin "A") (pinfunction "A_A") (pintype "passive"))
      (node (ref "T3") (pin "5") (pinfunction "P$5_5") (pintype "passive"))
    )
    (net (code "54") (name "Net-(T3-P$7)") (class "Default")
      (node (ref "D5") (pin "C") (pinfunction "C_C") (pintype "passive"))
      (node (ref "D6") (pin "A") (pinfunction "A_A") (pintype "passive"))
      (node (ref "T3") (pin "7") (pinfunction "P$7_7") (pintype "passive"))
    )
    (net (code "55") (name "Net-(T4-P$5)") (class "Default")
      (node (ref "D15") (pin "C") (pinfunction "C_C") (pintype "passive"))
      (node (ref "D16") (pin "A") (pinfunction "A_A") (pintype "passive"))
      (node (ref "T4") (pin "5") (pinfunction "P$5_5") (pintype "passive"))
    )
    (net (code "56") (name "Net-(T4-P$7)") (class "Default")
      (node (ref "D7") (pin "C") (pinfunction "C_C") (pintype "passive"))
      (node (ref "D8") (pin "A") (pinfunction "A_A") (pintype "passive"))
      (node (ref "T4") (pin "7") (pinfunction "P$7_7") (pintype "passive"))
    )
    (net (code "57") (name "Net-(T5-P$5)") (class "Default")
      (node (ref "D25") (pin "C") (pinfunction "C_C") (pintype "passive"))
      (node (ref "D26") (pin "A") (pinfunction "A_A") (pintype "passive"))
      (node (ref "T5") (pin "5") (pinfunction "P$5_5") (pintype "passive"))
    )
    (net (code "58") (name "Net-(T5-P$7)") (class "Default")
      (node (ref "D17") (pin "C") (pinfunction "C_C") (pintype "passive"))
      (node (ref "D18") (pin "A") (pinfunction "A_A") (pintype "passive"))
      (node (ref "T5") (pin "7") (pinfunction "P$7_7") (pintype "passive"))
    )
    (net (code "59") (name "Net-(T6-P$5)") (class "Default")
      (node (ref "D27") (pin "C") (pinfunction "C_C") (pintype "passive"))
      (node (ref "D28") (pin "A") (pinfunction "A_A") (pintype "passive"))
      (node (ref "T6") (pin "5") (pinfunction "P$5_5") (pintype "passive"))
    )
    (net (code "60") (name "Net-(T6-P$7)") (class "Default")
      (node (ref "D19") (pin "C") (pinfunction "C_C") (pintype "passive"))
      (node (ref "D20") (pin "A") (pinfunction "A_A") (pintype "passive"))
      (node (ref "T6") (pin "7") (pinfunction "P$7_7") (pintype "passive"))
    )
    (net (code "61") (name "Net-(T7-P$5)") (class "Default")
      (node (ref "D29") (pin "C") (pinfunction "C_C") (pintype "passive"))
      (node (ref "D30") (pin "A") (pinfunction "A_A") (pintype "passive"))
      (node (ref "T7") (pin "5") (pinfunction "P$5_5") (pintype "passive"))
    )
    (net (code "62") (name "Net-(T7-P$7)") (class "Default")
      (node (ref "D21") (pin "C") (pinfunction "C_C") (pintype "passive"))
      (node (ref "D22") (pin "A") (pinfunction "A_A") (pintype "passive"))
      (node (ref "T7") (pin "7") (pinfunction "P$7_7") (pintype "passive"))
    )
    (net (code "63") (name "Net-(T8-P$5)") (class "Default")
      (node (ref "D31") (pin "C") (pinfunction "C_C") (pintype "passive"))
      (node (ref "D32") (pin "A") (pinfunction "A_A") (pintype "passive"))
      (node (ref "T8") (pin "5") (pinfunction "P$5_5") (pintype "passive"))
    )
    (net (code "64") (name "Net-(T8-P$7)") (class "Default")
      (node (ref "D23") (pin "C") (pinfunction "C_C") (pintype "passive"))
      (node (ref "D24") (pin "A") (pinfunction "A_A") (pintype "passive"))
      (node (ref "T8") (pin "7") (pinfunction "P$7_7") (pintype "passive"))
    )
    (net (code "65") (name "Net-(T9-P$5)") (class "Default")
      (node (ref "D35") (pin "C") (pinfunction "C_C") (pintype "passive"))
      (node (ref "D36") (pin "A") (pinfunction "A_A") (pintype "passive"))
      (node (ref "T9") (pin "5") (pinfunction "P$5_5") (pintype "passive"))
    )
    (net (code "66") (name "Net-(T9-P$7)") (class "Default")
      (node (ref "D33") (pin "C") (pinfunction "C_C") (pintype "passive"))
      (node (ref "D34") (pin "A") (pinfunction "A_A") (pintype "passive"))
      (node (ref "T9") (pin "7") (pinfunction "P$7_7") (pintype "passive"))
    )
    (net (code "67") (name "Net-(T10-P$5)") (class "Default")
      (node (ref "D43") (pin "C") (pinfunction "C_C") (pintype "passive"))
      (node (ref "D44") (pin "A") (pinfunction "A_A") (pintype "passive"))
      (node (ref "T10") (pin "5") (pinfunction "P$5_5") (pintype "passive"))
    )
    (net (code "68") (name "Net-(T10-P$7)") (class "Default")
      (node (ref "D37") (pin "C") (pinfunction "C_C") (pintype "passive"))
      (node (ref "D38") (pin "A") (pinfunction "A_A") (pintype "passive"))
      (node (ref "T10") (pin "7") (pinfunction "P$7_7") (pintype "passive"))
    )
    (net (code "69") (name "Net-(T11-P$5)") (class "Default")
      (node (ref "D45") (pin "C") (pinfunction "C_C") (pintype "passive"))
      (node (ref "D46") (pin "A") (pinfunction "A_A") (pintype "passive"))
      (node (ref "T11") (pin "5") (pinfunction "P$5_5") (pintype "passive"))
    )
    (net (code "70") (name "Net-(T11-P$7)") (class "Default")
      (node (ref "D39") (pin "C") (pinfunction "C_C") (pintype "passive"))
      (node (ref "D40") (pin "A") (pinfunction "A_A") (pintype "passive"))
      (node (ref "T11") (pin "7") (pinfunction "P$7_7") (pintype "passive"))
    )
    (net (code "71") (name "Net-(T12-P$5)") (class "Default")
      (node (ref "D47") (pin "C") (pinfunction "C_C") (pintype "passive"))
      (node (ref "D48") (pin "A") (pinfunction "A_A") (pintype "passive"))
      (node (ref "T12") (pin "5") (pinfunction "P$5_5") (pintype "passive"))
    )
    (net (code "72") (name "Net-(T12-P$7)") (class "Default")
      (node (ref "D41") (pin "C") (pinfunction "C_C") (pintype "passive"))
      (node (ref "D42") (pin "A") (pinfunction "A_A") (pintype "passive"))
      (node (ref "T12") (pin "7") (pinfunction "P$7_7") (pintype "passive"))
    )
    (net (code "73") (name "Net-(T13-P$5)") (class "Default")
      (node (ref "D51") (pin "C") (pinfunction "C_C") (pintype "passive"))
      (node (ref "D52") (pin "A") (pinfunction "A_A") (pintype "passive"))
      (node (ref "T13") (pin "5") (pinfunction "P$5_5") (pintype "passive"))
    )
    (net (code "74") (name "Net-(T13-P$7)") (class "Default")
      (node (ref "D49") (pin "C") (pinfunction "C_C") (pintype "passive"))
      (node (ref "D50") (pin "A") (pinfunction "A_A") (pintype "passive"))
      (node (ref "T13") (pin "7") (pinfunction "P$7_7") (pintype "passive"))
    )
    (net (code "75") (name "Net-(T14-P$5)") (class "Default")
      (node (ref "D59") (pin "C") (pinfunction "C_C") (pintype "passive"))
      (node (ref "D60") (pin "A") (pinfunction "A_A") (pintype "passive"))
      (node (ref "T14") (pin "5") (pinfunction "P$5_5") (pintype "passive"))
    )
    (net (code "76") (name "Net-(T14-P$7)") (class "Default")
      (node (ref "D53") (pin "C") (pinfunction "C_C") (pintype "passive"))
      (node (ref "D54") (pin "A") (pinfunction "A_A") (pintype "passive"))
      (node (ref "T14") (pin "7") (pinfunction "P$7_7") (pintype "passive"))
    )
    (net (code "77") (name "Net-(T15-P$5)") (class "Default")
      (node (ref "D61") (pin "C") (pinfunction "C_C") (pintype "passive"))
      (node (ref "D62") (pin "A") (pinfunction "A_A") (pintype "passive"))
      (node (ref "T15") (pin "5") (pinfunction "P$5_5") (pintype "passive"))
    )
    (net (code "78") (name "Net-(T15-P$7)") (class "Default")
      (node (ref "D55") (pin "C") (pinfunction "C_C") (pintype "passive"))
      (node (ref "D56") (pin "A") (pinfunction "A_A") (pintype "passive"))
      (node (ref "T15") (pin "7") (pinfunction "P$7_7") (pintype "passive"))
    )
    (net (code "79") (name "Net-(T16-P$5)") (class "Default")
      (node (ref "D63") (pin "C") (pinfunction "C_C") (pintype "passive"))
      (node (ref "D64") (pin "A") (pinfunction "A_A") (pintype "passive"))
      (node (ref "T16") (pin "5") (pinfunction "P$5_5") (pintype "passive"))
    )
    (net (code "80") (name "Net-(T16-P$7)") (class "Default")
      (node (ref "D57") (pin "C") (pinfunction "C_C") (pintype "passive"))
      (node (ref "D58") (pin "A") (pinfunction "A_A") (pintype "passive"))
      (node (ref "T16") (pin "7") (pinfunction "P$7_7") (pintype "passive"))
    )
  )
)
